# Sheet5.net
KiCad netlist of a schematic drawn in Altium Designer
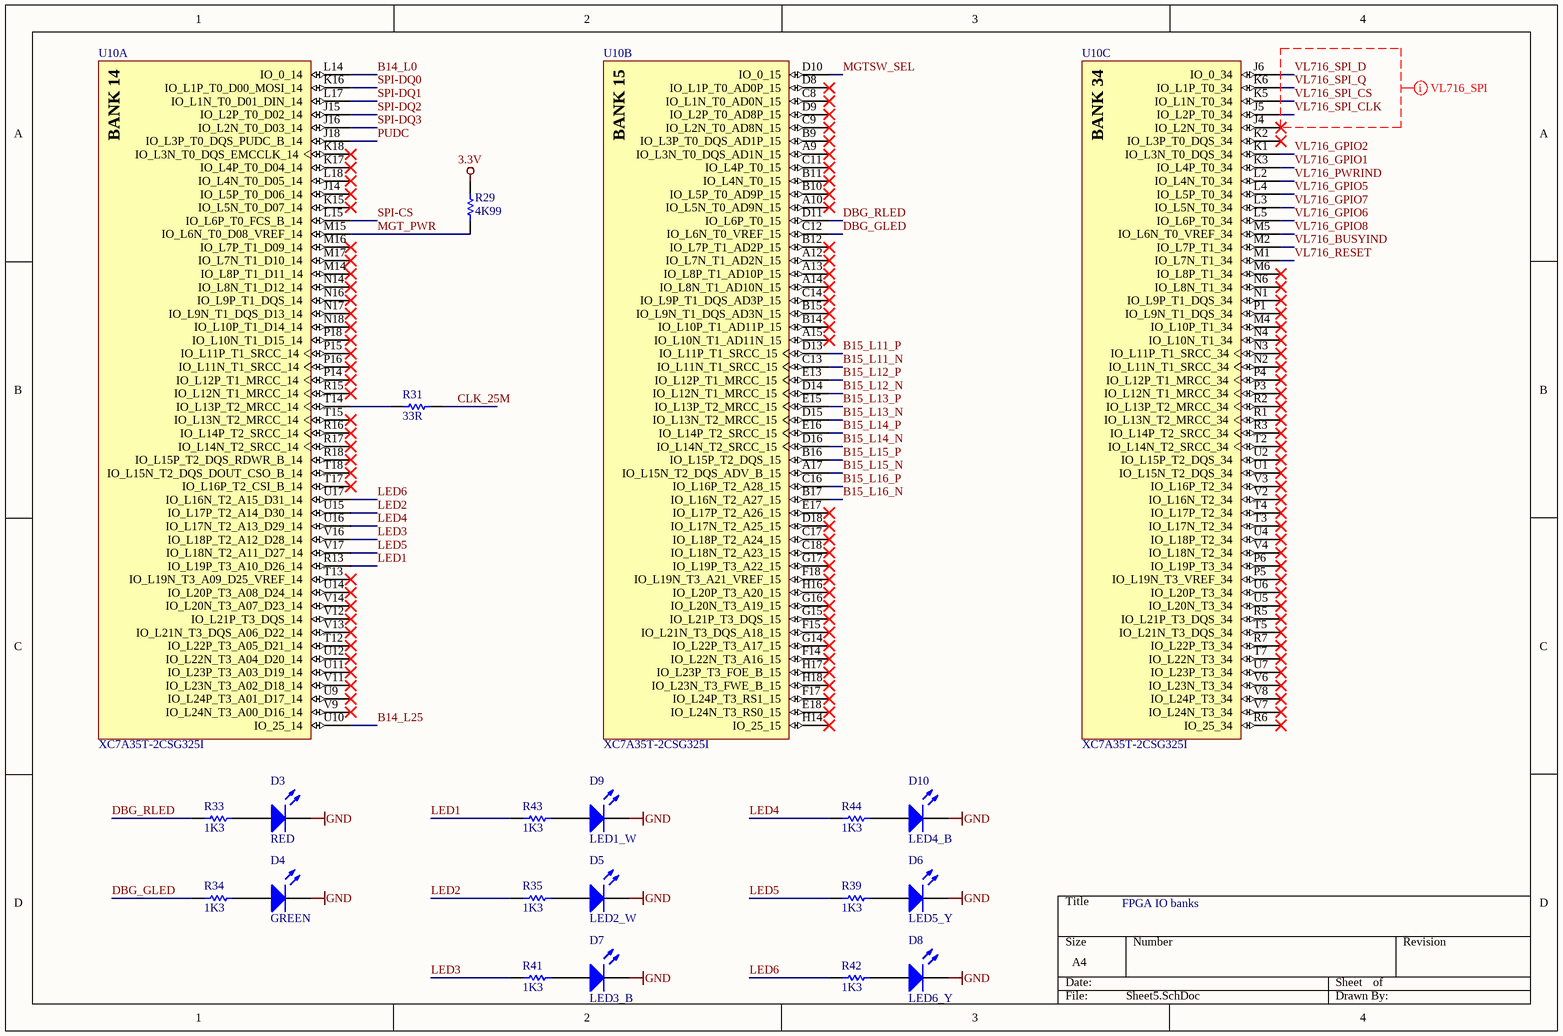
[diagram p0: Sheet5.SchDoc]

(export (version "E")
  (design (tool "Eeschema 10.0.6"))
  (components
    (comp (ref "D3")
      (value "RED")
      (footprint "LEDC2012X10N")
      (description "SMD chip LED")
      (libsource (lib "Integrated_Library") (part "LED0805"))
    )
    (comp (ref "D4")
      (value "GREEN")
      (footprint "LEDC2012X10N")
      (description "SMD chip LED")
      (libsource (lib "Integrated_Library") (part "LED0805"))
    )
    (comp (ref "D5")
      (value "LED2_W")
      (footprint "LEDC2012X10N")
      (description "SMD chip LED")
      (libsource (lib "Integrated_Library") (part "LED0805"))
    )
    (comp (ref "D6")
      (value "LED5_Y")
      (footprint "LEDC2012X10N")
      (description "SMD chip LED")
      (libsource (lib "Integrated_Library") (part "LED0805"))
    )
    (comp (ref "D7")
      (value "LED3_B")
      (footprint "LEDC2012X10N")
      (description "SMD chip LED")
      (libsource (lib "Integrated_Library") (part "LED0805"))
    )
    (comp (ref "D8")
      (value "LED6_Y")
      (footprint "LEDC2012X10N")
      (description "SMD chip LED")
      (libsource (lib "Integrated_Library") (part "LED0805"))
    )
    (comp (ref "D9")
      (value "LED1_W")
      (footprint "LEDC2012X10N")
      (description "SMD chip LED")
      (libsource (lib "Integrated_Library") (part "LED0805"))
    )
    (comp (ref "D10")
      (value "LED4_B")
      (footprint "LEDC2012X10N")
      (description "SMD chip LED")
      (libsource (lib "Integrated_Library") (part "LED0805"))
    )
    (comp (ref "R29")
      (value "4K99")
      (footprint "RESC1005X05N")
      (description "Ceramic Chip Resistor")
      (libsource (lib "Integrated_Library") (part "R0402"))
    )
    (comp (ref "R31")
      (value "33R")
      (footprint "RESC1005X05N")
      (description "Ceramic Chip Resistor")
      (libsource (lib "Integrated_Library") (part "R0402"))
    )
    (comp (ref "R33")
      (value "1K3")
      (footprint "RESC1005X05N")
      (description "Ceramic Chip Resistor")
      (libsource (lib "Integrated_Library") (part "R0402"))
    )
    (comp (ref "R34")
      (value "1K3")
      (footprint "RESC1005X05N")
      (description "Ceramic Chip Resistor")
      (libsource (lib "Integrated_Library") (part "R0402"))
    )
    (comp (ref "R35")
      (value "1K3")
      (footprint "RESC1005X05N")
      (description "Ceramic Chip Resistor")
      (libsource (lib "Integrated_Library") (part "R0402"))
    )
    (comp (ref "R39")
      (value "1K3")
      (footprint "RESC1005X05N")
      (description "Ceramic Chip Resistor")
      (libsource (lib "Integrated_Library") (part "R0402"))
    )
    (comp (ref "R41")
      (value "1K3")
      (footprint "RESC1005X05N")
      (description "Ceramic Chip Resistor")
      (libsource (lib "Integrated_Library") (part "R0402"))
    )
    (comp (ref "R42")
      (value "1K3")
      (footprint "RESC1005X05N")
      (description "Ceramic Chip Resistor")
      (libsource (lib "Integrated_Library") (part "R0402"))
    )
    (comp (ref "R43")
      (value "1K3")
      (footprint "RESC1005X05N")
      (description "Ceramic Chip Resistor")
      (libsource (lib "Integrated_Library") (part "R0402"))
    )
    (comp (ref "R44")
      (value "1K3")
      (footprint "RESC1005X05N")
      (description "Ceramic Chip Resistor")
      (libsource (lib "Integrated_Library") (part "R0402"))
    )
    (comp (ref "U10")
      (value "XC7A35T-2CSG325I")
      (footprint "XC7A35T-2CSG325I")
      (description "Artix-7 FPGA, 150 User I/Os, 4 GTP, 324-Ball BGA, Speed Grade 2, Industrial Grade, Pb-Free")
      (fields (field (name "MANUFACTURER") "Xilinx"))
      (libsource (lib "Integrated_Library") (part "XC7A35T-2CSG325I"))
    )
  )
  (nets
    (net (code "1") (name "/B14_L0") (class "Default")
      (node (ref "U10") (pin "L14") (pinfunction "IO_0_14_L14") (pintype "bidirectional"))
    )
    (net (code "2") (name "/B14_L25") (class "Default")
      (node (ref "U10") (pin "U10") (pinfunction "IO_25_14_U10") (pintype "bidirectional"))
    )
    (net (code "3") (name "/B15_L11_N") (class "Default")
      (node (ref "U10") (pin "C13") (pinfunction "IO_L11N_T1_SRCC_15_C13") (pintype "bidirectional"))
    )
    (net (code "4") (name "/B15_L11_P") (class "Default")
      (node (ref "U10") (pin "D13") (pinfunction "IO_L11P_T1_SRCC_15_D13") (pintype "bidirectional"))
    )
    (net (code "5") (name "/B15_L12_N") (class "Default")
      (node (ref "U10") (pin "D14") (pinfunction "IO_L12N_T1_MRCC_15_D14") (pintype "bidirectional"))
    )
    (net (code "6") (name "/B15_L12_P") (class "Default")
      (node (ref "U10") (pin "E13") (pinfunction "IO_L12P_T1_MRCC_15_E13") (pintype "bidirectional"))
    )
    (net (code "7") (name "/B15_L13_N") (class "Default")
      (node (ref "U10") (pin "D15") (pinfunction "IO_L13N_T2_MRCC_15_D15") (pintype "bidirectional"))
    )
    (net (code "8") (name "/B15_L13_P") (class "Default")
      (node (ref "U10") (pin "E15") (pinfunction "IO_L13P_T2_MRCC_15_E15") (pintype "bidirectional"))
    )
    (net (code "9") (name "/B15_L14_N") (class "Default")
      (node (ref "U10") (pin "D16") (pinfunction "IO_L14N_T2_SRCC_15_D16") (pintype "bidirectional"))
    )
    (net (code "10") (name "/B15_L14_P") (class "Default")
      (node (ref "U10") (pin "E16") (pinfunction "IO_L14P_T2_SRCC_15_E16") (pintype "bidirectional"))
    )
    (net (code "11") (name "/B15_L15_N") (class "Default")
      (node (ref "U10") (pin "A17") (pinfunction "IO_L15N_T2_DQS_ADV_B_15_A17") (pintype "bidirectional"))
    )
    (net (code "12") (name "/B15_L15_P") (class "Default")
      (node (ref "U10") (pin "B16") (pinfunction "IO_L15P_T2_DQS_15_B16") (pintype "bidirectional"))
    )
    (net (code "13") (name "/B15_L16_N") (class "Default")
      (node (ref "U10") (pin "B17") (pinfunction "IO_L16N_T2_A27_15_B17") (pintype "bidirectional"))
    )
    (net (code "14") (name "/B15_L16_P") (class "Default")
      (node (ref "U10") (pin "C16") (pinfunction "IO_L16P_T2_A28_15_C16") (pintype "bidirectional"))
    )
    (net (code "15") (name "/CLK_25M") (class "Default")
      (node (ref "R31") (pin "2") (pinfunction "2_2") (pintype "passive"))
    )
    (net (code "16") (name "/DBG_GLED") (class "Default")
      (node (ref "R34") (pin "2") (pinfunction "2_2") (pintype "passive"))
      (node (ref "U10") (pin "C12") (pinfunction "IO_L6N_T0_VREF_15_C12") (pintype "bidirectional"))
    )
    (net (code "17") (name "/DBG_RLED") (class "Default")
      (node (ref "R33") (pin "2") (pinfunction "2_2") (pintype "passive"))
      (node (ref "U10") (pin "D11") (pinfunction "IO_L6P_T0_15_D11") (pintype "bidirectional"))
    )
    (net (code "18") (name "/LED1") (class "Default")
      (node (ref "R43") (pin "2") (pinfunction "2_2") (pintype "passive"))
      (node (ref "U10") (pin "R13") (pinfunction "IO_L19P_T3_A10_D26_14_R13") (pintype "bidirectional"))
    )
    (net (code "19") (name "/LED2") (class "Default")
      (node (ref "R35") (pin "2") (pinfunction "2_2") (pintype "passive"))
      (node (ref "U10") (pin "U15") (pinfunction "IO_L17P_T2_A14_D30_14_U15") (pintype "bidirectional"))
    )
    (net (code "20") (name "/LED3") (class "Default")
      (node (ref "R41") (pin "2") (pinfunction "2_2") (pintype "passive"))
      (node (ref "U10") (pin "V16") (pinfunction "IO_L18P_T2_A12_D28_14_V16") (pintype "bidirectional"))
    )
    (net (code "21") (name "/LED4") (class "Default")
      (node (ref "R44") (pin "2") (pinfunction "2_2") (pintype "passive"))
      (node (ref "U10") (pin "U16") (pinfunction "IO_L17N_T2_A13_D29_14_U16") (pintype "bidirectional"))
    )
    (net (code "22") (name "/LED5") (class "Default")
      (node (ref "R39") (pin "2") (pinfunction "2_2") (pintype "passive"))
      (node (ref "U10") (pin "V17") (pinfunction "IO_L18N_T2_A11_D27_14_V17") (pintype "bidirectional"))
    )
    (net (code "23") (name "/LED6") (class "Default")
      (node (ref "R42") (pin "2") (pinfunction "2_2") (pintype "passive"))
      (node (ref "U10") (pin "U17") (pinfunction "IO_L16N_T2_A15_D31_14_U17") (pintype "bidirectional"))
    )
    (net (code "24") (name "/MGTSW_SEL") (class "Default")
      (node (ref "U10") (pin "D10") (pinfunction "IO_0_15_D10") (pintype "bidirectional"))
    )
    (net (code "25") (name "/MGT_PWR") (class "Default")
      (node (ref "R29") (pin "2") (pinfunction "2_2") (pintype "passive"))
      (node (ref "U10") (pin "M15") (pinfunction "IO_L6N_T0_D08_VREF_14_M15") (pintype "bidirectional"))
    )
    (net (code "26") (name "/PUDC") (class "Default")
      (node (ref "U10") (pin "J18") (pinfunction "IO_L3P_T0_DQS_PUDC_B_14_J18") (pintype "bidirectional"))
    )
    (net (code "27") (name "/SPI-CS") (class "Default")
      (node (ref "U10") (pin "L15") (pinfunction "IO_L6P_T0_FCS_B_14_L15") (pintype "bidirectional"))
    )
    (net (code "28") (name "/SPI-DQ0") (class "Default")
      (node (ref "U10") (pin "K16") (pinfunction "IO_L1P_T0_D00_MOSI_14_K16") (pintype "bidirectional"))
    )
    (net (code "29") (name "/SPI-DQ1") (class "Default")
      (node (ref "U10") (pin "L17") (pinfunction "IO_L1N_T0_D01_DIN_14_L17") (pintype "bidirectional"))
    )
    (net (code "30") (name "/SPI-DQ2") (class "Default")
      (node (ref "U10") (pin "J15") (pinfunction "IO_L2P_T0_D02_14_J15") (pintype "bidirectional"))
    )
    (net (code "31") (name "/SPI-DQ3") (class "Default")
      (node (ref "U10") (pin "J16") (pinfunction "IO_L2N_T0_D03_14_J16") (pintype "bidirectional"))
    )
    (net (code "32") (name "/VL716_BUSYIND") (class "Default")
      (node (ref "U10") (pin "M2") (pinfunction "IO_L7P_T1_34_M2") (pintype "bidirectional"))
    )
    (net (code "33") (name "/VL716_GPIO1") (class "Default")
      (node (ref "U10") (pin "K3") (pinfunction "IO_L4P_T0_34_K3") (pintype "bidirectional"))
    )
    (net (code "34") (name "/VL716_GPIO2") (class "Default")
      (node (ref "U10") (pin "K1") (pinfunction "IO_L3N_T0_DQS_34_K1") (pintype "bidirectional"))
    )
    (net (code "35") (name "/VL716_GPIO5") (class "Default")
      (node (ref "U10") (pin "L4") (pinfunction "IO_L5P_T0_34_L4") (pintype "bidirectional"))
    )
    (net (code "36") (name "/VL716_GPIO6") (class "Default")
      (node (ref "U10") (pin "L5") (pinfunction "IO_L6P_T0_34_L5") (pintype "bidirectional"))
    )
    (net (code "37") (name "/VL716_GPIO7") (class "Default")
      (node (ref "U10") (pin "L3") (pinfunction "IO_L5N_T0_34_L3") (pintype "bidirectional"))
    )
    (net (code "38") (name "/VL716_GPIO8") (class "Default")
      (node (ref "U10") (pin "M5") (pinfunction "IO_L6N_T0_VREF_34_M5") (pintype "bidirectional"))
    )
    (net (code "39") (name "/VL716_PWRIND") (class "Default")
      (node (ref "U10") (pin "L2") (pinfunction "IO_L4N_T0_34_L2") (pintype "bidirectional"))
    )
    (net (code "40") (name "/VL716_RESET") (class "Default")
      (node (ref "U10") (pin "M1") (pinfunction "IO_L7N_T1_34_M1") (pintype "bidirectional"))
    )
    (net (code "41") (name "/VL716_SPI_CLK") (class "Default")
      (node (ref "U10") (pin "J5") (pinfunction "IO_L2P_T0_34_J5") (pintype "bidirectional"))
    )
    (net (code "42") (name "/VL716_SPI_CS") (class "Default")
      (node (ref "U10") (pin "K5") (pinfunction "IO_L1N_T0_34_K5") (pintype "bidirectional"))
    )
    (net (code "43") (name "/VL716_SPI_D") (class "Default")
      (node (ref "U10") (pin "J6") (pinfunction "IO_0_34_J6") (pintype "bidirectional"))
    )
    (net (code "44") (name "/VL716_SPI_Q") (class "Default")
      (node (ref "U10") (pin "K6") (pinfunction "IO_L1P_T0_34_K6") (pintype "bidirectional"))
    )
    (net (code "45") (name "3.3V") (class "Default")
      (node (ref "R29") (pin "1") (pinfunction "1_1") (pintype "passive"))
    )
    (net (code "46") (name "GND") (class "Default")
      (node (ref "D10") (pin "1") (pinfunction "K_1") (pintype "passive"))
      (node (ref "D3") (pin "1") (pinfunction "K_1") (pintype "passive"))
      (node (ref "D4") (pin "1") (pinfunction "K_1") (pintype "passive"))
      (node (ref "D5") (pin "1") (pinfunction "K_1") (pintype "passive"))
      (node (ref "D6") (pin "1") (pinfunction "K_1") (pintype "passive"))
      (node (ref "D7") (pin "1") (pinfunction "K_1") (pintype "passive"))
      (node (ref "D8") (pin "1") (pinfunction "K_1") (pintype "passive"))
      (node (ref "D9") (pin "1") (pinfunction "K_1") (pintype "passive"))
    )
    (net (code "47") (name "Net-(D3-A)") (class "Default")
      (node (ref "D3") (pin "2") (pinfunction "A_2") (pintype "passive"))
      (node (ref "R33") (pin "1") (pinfunction "1_1") (pintype "passive"))
    )
    (net (code "48") (name "Net-(D4-A)") (class "Default")
      (node (ref "D4") (pin "2") (pinfunction "A_2") (pintype "passive"))
      (node (ref "R34") (pin "1") (pinfunction "1_1") (pintype "passive"))
    )
    (net (code "49") (name "Net-(D5-A)") (class "Default")
      (node (ref "D5") (pin "2") (pinfunction "A_2") (pintype "passive"))
      (node (ref "R35") (pin "1") (pinfunction "1_1") (pintype "passive"))
    )
    (net (code "50") (name "Net-(D6-A)") (class "Default")
      (node (ref "D6") (pin "2") (pinfunction "A_2") (pintype "passive"))
      (node (ref "R39") (pin "1") (pinfunction "1_1") (pintype "passive"))
    )
    (net (code "51") (name "Net-(D7-A)") (class "Default")
      (node (ref "D7") (pin "2") (pinfunction "A_2") (pintype "passive"))
      (node (ref "R41") (pin "1") (pinfunction "1_1") (pintype "passive"))
    )
    (net (code "52") (name "Net-(D8-A)") (class "Default")
      (node (ref "D8") (pin "2") (pinfunction "A_2") (pintype "passive"))
      (node (ref "R42") (pin "1") (pinfunction "1_1") (pintype "passive"))
    )
    (net (code "53") (name "Net-(D9-A)") (class "Default")
      (node (ref "D9") (pin "2") (pinfunction "A_2") (pintype "passive"))
      (node (ref "R43") (pin "1") (pinfunction "1_1") (pintype "passive"))
    )
    (net (code "54") (name "Net-(D10-A)") (class "Default")
      (node (ref "D10") (pin "2") (pinfunction "A_2") (pintype "passive"))
      (node (ref "R44") (pin "1") (pinfunction "1_1") (pintype "passive"))
    )
    (net (code "55") (name "Net-(U10A-IO_L13P_T2_MRCC_14)") (class "Default")
      (node (ref "R31") (pin "1") (pinfunction "1_1") (pintype "passive"))
      (node (ref "U10") (pin "T14") (pinfunction "IO_L13P_T2_MRCC_14_T14") (pintype "bidirectional"))
    )
    (net (code "56") (name "unconnected-(U10A-IO_L3N_T0_DQS_EMCCLK_14-PadK18)") (class "Default")
      (node (ref "U10") (pin "K18") (pinfunction "IO_L3N_T0_DQS_EMCCLK_14_K18") (pintype "bidirectional+no_connect"))
    )
    (net (code "57") (name "unconnected-(U10A-IO_L4N_T0_D05_14-PadL18)") (class "Default")
      (node (ref "U10") (pin "L18") (pinfunction "IO_L4N_T0_D05_14_L18") (pintype "bidirectional+no_connect"))
    )
    (net (code "58") (name "unconnected-(U10A-IO_L4P_T0_D04_14-PadK17)") (class "Default")
      (node (ref "U10") (pin "K17") (pinfunction "IO_L4P_T0_D04_14_K17") (pintype "bidirectional+no_connect"))
    )
    (net (code "59") (name "unconnected-(U10A-IO_L5N_T0_D07_14-PadK15)") (class "Default")
      (node (ref "U10") (pin "K15") (pinfunction "IO_L5N_T0_D07_14_K15") (pintype "bidirectional+no_connect"))
    )
    (net (code "60") (name "unconnected-(U10A-IO_L5P_T0_D06_14-PadJ14)") (class "Default")
      (node (ref "U10") (pin "J14") (pinfunction "IO_L5P_T0_D06_14_J14") (pintype "bidirectional+no_connect"))
    )
    (net (code "61") (name "unconnected-(U10A-IO_L7N_T1_D10_14-PadM17)") (class "Default")
      (node (ref "U10") (pin "M17") (pinfunction "IO_L7N_T1_D10_14_M17") (pintype "bidirectional+no_connect"))
    )
    (net (code "62") (name "unconnected-(U10A-IO_L7P_T1_D09_14-PadM16)") (class "Default")
      (node (ref "U10") (pin "M16") (pinfunction "IO_L7P_T1_D09_14_M16") (pintype "bidirectional+no_connect"))
    )
    (net (code "63") (name "unconnected-(U10A-IO_L8N_T1_D12_14-PadN14)") (class "Default")
      (node (ref "U10") (pin "N14") (pinfunction "IO_L8N_T1_D12_14_N14") (pintype "bidirectional+no_connect"))
    )
    (net (code "64") (name "unconnected-(U10A-IO_L8P_T1_D11_14-PadM14)") (class "Default")
      (node (ref "U10") (pin "M14") (pinfunction "IO_L8P_T1_D11_14_M14") (pintype "bidirectional+no_connect"))
    )
    (net (code "65") (name "unconnected-(U10A-IO_L9N_T1_DQS_D13_14-PadN17)") (class "Default")
      (node (ref "U10") (pin "N17") (pinfunction "IO_L9N_T1_DQS_D13_14_N17") (pintype "bidirectional+no_connect"))
    )
    (net (code "66") (name "unconnected-(U10A-IO_L9P_T1_DQS_14-PadN16)") (class "Default")
      (node (ref "U10") (pin "N16") (pinfunction "IO_L9P_T1_DQS_14_N16") (pintype "bidirectional+no_connect"))
    )
    (net (code "67") (name "unconnected-(U10A-IO_L10N_T1_D15_14-PadP18)") (class "Default")
      (node (ref "U10") (pin "P18") (pinfunction "IO_L10N_T1_D15_14_P18") (pintype "bidirectional+no_connect"))
    )
    (net (code "68") (name "unconnected-(U10A-IO_L10P_T1_D14_14-PadN18)") (class "Default")
      (node (ref "U10") (pin "N18") (pinfunction "IO_L10P_T1_D14_14_N18") (pintype "bidirectional+no_connect"))
    )
    (net (code "69") (name "unconnected-(U10A-IO_L11N_T1_SRCC_14-PadP16)") (class "Default")
      (node (ref "U10") (pin "P16") (pinfunction "IO_L11N_T1_SRCC_14_P16") (pintype "bidirectional+no_connect"))
    )
    (net (code "70") (name "unconnected-(U10A-IO_L11P_T1_SRCC_14-PadP15)") (class "Default")
      (node (ref "U10") (pin "P15") (pinfunction "IO_L11P_T1_SRCC_14_P15") (pintype "bidirectional+no_connect"))
    )
    (net (code "71") (name "unconnected-(U10A-IO_L12N_T1_MRCC_14-PadR15)") (class "Default")
      (node (ref "U10") (pin "R15") (pinfunction "IO_L12N_T1_MRCC_14_R15") (pintype "bidirectional+no_connect"))
    )
    (net (code "72") (name "unconnected-(U10A-IO_L12P_T1_MRCC_14-PadP14)") (class "Default")
      (node (ref "U10") (pin "P14") (pinfunction "IO_L12P_T1_MRCC_14_P14") (pintype "bidirectional+no_connect"))
    )
    (net (code "73") (name "unconnected-(U10A-IO_L13N_T2_MRCC_14-PadT15)") (class "Default")
      (node (ref "U10") (pin "T15") (pinfunction "IO_L13N_T2_MRCC_14_T15") (pintype "bidirectional+no_connect"))
    )
    (net (code "74") (name "unconnected-(U10A-IO_L14N_T2_SRCC_14-PadR17)") (class "Default")
      (node (ref "U10") (pin "R17") (pinfunction "IO_L14N_T2_SRCC_14_R17") (pintype "bidirectional+no_connect"))
    )
    (net (code "75") (name "unconnected-(U10A-IO_L14P_T2_SRCC_14-PadR16)") (class "Default")
      (node (ref "U10") (pin "R16") (pinfunction "IO_L14P_T2_SRCC_14_R16") (pintype "bidirectional+no_connect"))
    )
    (net (code "76") (name "unconnected-(U10A-IO_L15N_T2_DQS_DOUT_CSO_B_14-PadT18)") (class "Default")
      (node (ref "U10") (pin "T18") (pinfunction "IO_L15N_T2_DQS_DOUT_CSO_B_14_T18") (pintype "bidirectional+no_connect"))
    )
    (net (code "77") (name "unconnected-(U10A-IO_L15P_T2_DQS_RDWR_B_14-PadR18)") (class "Default")
      (node (ref "U10") (pin "R18") (pinfunction "IO_L15P_T2_DQS_RDWR_B_14_R18") (pintype "bidirectional+no_connect"))
    )
    (net (code "78") (name "unconnected-(U10A-IO_L16P_T2_CSI_B_14-PadT17)") (class "Default")
      (node (ref "U10") (pin "T17") (pinfunction "IO_L16P_T2_CSI_B_14_T17") (pintype "bidirectional+no_connect"))
    )
    (net (code "79") (name "unconnected-(U10A-IO_L19N_T3_A09_D25_VREF_14-PadT13)") (class "Default")
      (node (ref "U10") (pin "T13") (pinfunction "IO_L19N_T3_A09_D25_VREF_14_T13") (pintype "bidirectional+no_connect"))
    )
    (net (code "80") (name "unconnected-(U10A-IO_L20N_T3_A07_D23_14-PadV14)") (class "Default")
      (node (ref "U10") (pin "V14") (pinfunction "IO_L20N_T3_A07_D23_14_V14") (pintype "bidirectional+no_connect"))
    )
    (net (code "81") (name "unconnected-(U10A-IO_L20P_T3_A08_D24_14-PadU14)") (class "Default")
      (node (ref "U10") (pin "U14") (pinfunction "IO_L20P_T3_A08_D24_14_U14") (pintype "bidirectional+no_connect"))
    )
    (net (code "82") (name "unconnected-(U10A-IO_L21N_T3_DQS_A06_D22_14-PadV13)") (class "Default")
      (node (ref "U10") (pin "V13") (pinfunction "IO_L21N_T3_DQS_A06_D22_14_V13") (pintype "bidirectional+no_connect"))
    )
    (net (code "83") (name "unconnected-(U10A-IO_L21P_T3_DQS_14-PadV12)") (class "Default")
      (node (ref "U10") (pin "V12") (pinfunction "IO_L21P_T3_DQS_14_V12") (pintype "bidirectional+no_connect"))
    )
    (net (code "84") (name "unconnected-(U10A-IO_L22N_T3_A04_D20_14-PadU12)") (class "Default")
      (node (ref "U10") (pin "U12") (pinfunction "IO_L22N_T3_A04_D20_14_U12") (pintype "bidirectional+no_connect"))
    )
    (net (code "85") (name "unconnected-(U10A-IO_L22P_T3_A05_D21_14-PadT12)") (class "Default")
      (node (ref "U10") (pin "T12") (pinfunction "IO_L22P_T3_A05_D21_14_T12") (pintype "bidirectional+no_connect"))
    )
    (net (code "86") (name "unconnected-(U10A-IO_L23N_T3_A02_D18_14-PadV11)") (class "Default")
      (node (ref "U10") (pin "V11") (pinfunction "IO_L23N_T3_A02_D18_14_V11") (pintype "bidirectional+no_connect"))
    )
    (net (code "87") (name "unconnected-(U10A-IO_L23P_T3_A03_D19_14-PadU11)") (class "Default")
      (node (ref "U10") (pin "U11") (pinfunction "IO_L23P_T3_A03_D19_14_U11") (pintype "bidirectional+no_connect"))
    )
    (net (code "88") (name "unconnected-(U10A-IO_L24N_T3_A00_D16_14-PadV9)") (class "Default")
      (node (ref "U10") (pin "V9") (pinfunction "IO_L24N_T3_A00_D16_14_V9") (pintype "bidirectional+no_connect"))
    )
    (net (code "89") (name "unconnected-(U10A-IO_L24P_T3_A01_D17_14-PadU9)") (class "Default")
      (node (ref "U10") (pin "U9") (pinfunction "IO_L24P_T3_A01_D17_14_U9") (pintype "bidirectional+no_connect"))
    )
    (net (code "90") (name "unconnected-(U10B-IO_25_15-PadH14)") (class "Default")
      (node (ref "U10") (pin "H14") (pinfunction "IO_25_15_H14") (pintype "bidirectional+no_connect"))
    )
    (net (code "91") (name "unconnected-(U10B-IO_L1N_T0_AD0N_15-PadC8)") (class "Default")
      (node (ref "U10") (pin "C8") (pinfunction "IO_L1N_T0_AD0N_15_C8") (pintype "bidirectional+no_connect"))
    )
    (net (code "92") (name "unconnected-(U10B-IO_L1P_T0_AD0P_15-PadD8)") (class "Default")
      (node (ref "U10") (pin "D8") (pinfunction "IO_L1P_T0_AD0P_15_D8") (pintype "bidirectional+no_connect"))
    )
    (net (code "93") (name "unconnected-(U10B-IO_L2N_T0_AD8N_15-PadC9)") (class "Default")
      (node (ref "U10") (pin "C9") (pinfunction "IO_L2N_T0_AD8N_15_C9") (pintype "bidirectional+no_connect"))
    )
    (net (code "94") (name "unconnected-(U10B-IO_L2P_T0_AD8P_15-PadD9)") (class "Default")
      (node (ref "U10") (pin "D9") (pinfunction "IO_L2P_T0_AD8P_15_D9") (pintype "bidirectional+no_connect"))
    )
    (net (code "95") (name "unconnected-(U10B-IO_L3N_T0_DQS_AD1N_15-PadA9)") (class "Default")
      (node (ref "U10") (pin "A9") (pinfunction "IO_L3N_T0_DQS_AD1N_15_A9") (pintype "bidirectional+no_connect"))
    )
    (net (code "96") (name "unconnected-(U10B-IO_L3P_T0_DQS_AD1P_15-PadB9)") (class "Default")
      (node (ref "U10") (pin "B9") (pinfunction "IO_L3P_T0_DQS_AD1P_15_B9") (pintype "bidirectional+no_connect"))
    )
    (net (code "97") (name "unconnected-(U10B-IO_L4N_T0_15-PadB11)") (class "Default")
      (node (ref "U10") (pin "B11") (pinfunction "IO_L4N_T0_15_B11") (pintype "bidirectional+no_connect"))
    )
    (net (code "98") (name "unconnected-(U10B-IO_L4P_T0_15-PadC11)") (class "Default")
      (node (ref "U10") (pin "C11") (pinfunction "IO_L4P_T0_15_C11") (pintype "bidirectional+no_connect"))
    )
    (net (code "99") (name "unconnected-(U10B-IO_L5N_T0_AD9N_15-PadA10)") (class "Default")
      (node (ref "U10") (pin "A10") (pinfunction "IO_L5N_T0_AD9N_15_A10") (pintype "bidirectional+no_connect"))
    )
    (net (code "100") (name "unconnected-(U10B-IO_L5P_T0_AD9P_15-PadB10)") (class "Default")
      (node (ref "U10") (pin "B10") (pinfunction "IO_L5P_T0_AD9P_15_B10") (pintype "bidirectional+no_connect"))
    )
    (net (code "101") (name "unconnected-(U10B-IO_L7N_T1_AD2N_15-PadA12)") (class "Default")
      (node (ref "U10") (pin "A12") (pinfunction "IO_L7N_T1_AD2N_15_A12") (pintype "bidirectional+no_connect"))
    )
    (net (code "102") (name "unconnected-(U10B-IO_L7P_T1_AD2P_15-PadB12)") (class "Default")
      (node (ref "U10") (pin "B12") (pinfunction "IO_L7P_T1_AD2P_15_B12") (pintype "bidirectional+no_connect"))
    )
    (net (code "103") (name "unconnected-(U10B-IO_L8N_T1_AD10N_15-PadA14)") (class "Default")
      (node (ref "U10") (pin "A14") (pinfunction "IO_L8N_T1_AD10N_15_A14") (pintype "bidirectional+no_connect"))
    )
    (net (code "104") (name "unconnected-(U10B-IO_L8P_T1_AD10P_15-PadA13)") (class "Default")
      (node (ref "U10") (pin "A13") (pinfunction "IO_L8P_T1_AD10P_15_A13") (pintype "bidirectional+no_connect"))
    )
    (net (code "105") (name "unconnected-(U10B-IO_L9N_T1_DQS_AD3N_15-PadB15)") (class "Default")
      (node (ref "U10") (pin "B15") (pinfunction "IO_L9N_T1_DQS_AD3N_15_B15") (pintype "bidirectional+no_connect"))
    )
    (net (code "106") (name "unconnected-(U10B-IO_L9P_T1_DQS_AD3P_15-PadC14)") (class "Default")
      (node (ref "U10") (pin "C14") (pinfunction "IO_L9P_T1_DQS_AD3P_15_C14") (pintype "bidirectional+no_connect"))
    )
    (net (code "107") (name "unconnected-(U10B-IO_L10N_T1_AD11N_15-PadA15)") (class "Default")
      (node (ref "U10") (pin "A15") (pinfunction "IO_L10N_T1_AD11N_15_A15") (pintype "bidirectional+no_connect"))
    )
    (net (code "108") (name "unconnected-(U10B-IO_L10P_T1_AD11P_15-PadB14)") (class "Default")
      (node (ref "U10") (pin "B14") (pinfunction "IO_L10P_T1_AD11P_15_B14") (pintype "bidirectional+no_connect"))
    )
    (net (code "109") (name "unconnected-(U10B-IO_L17N_T2_A25_15-PadD18)") (class "Default")
      (node (ref "U10") (pin "D18") (pinfunction "IO_L17N_T2_A25_15_D18") (pintype "bidirectional+no_connect"))
    )
    (net (code "110") (name "unconnected-(U10B-IO_L17P_T2_A26_15-PadE17)") (class "Default")
      (node (ref "U10") (pin "E17") (pinfunction "IO_L17P_T2_A26_15_E17") (pintype "bidirectional+no_connect"))
    )
    (net (code "111") (name "unconnected-(U10B-IO_L18N_T2_A23_15-PadC18)") (class "Default")
      (node (ref "U10") (pin "C18") (pinfunction "IO_L18N_T2_A23_15_C18") (pintype "bidirectional+no_connect"))
    )
    (net (code "112") (name "unconnected-(U10B-IO_L18P_T2_A24_15-PadC17)") (class "Default")
      (node (ref "U10") (pin "C17") (pinfunction "IO_L18P_T2_A24_15_C17") (pintype "bidirectional+no_connect"))
    )
    (net (code "113") (name "unconnected-(U10B-IO_L19N_T3_A21_VREF_15-PadF18)") (class "Default")
      (node (ref "U10") (pin "F18") (pinfunction "IO_L19N_T3_A21_VREF_15_F18") (pintype "bidirectional+no_connect"))
    )
    (net (code "114") (name "unconnected-(U10B-IO_L19P_T3_A22_15-PadG17)") (class "Default")
      (node (ref "U10") (pin "G17") (pinfunction "IO_L19P_T3_A22_15_G17") (pintype "bidirectional+no_connect"))
    )
    (net (code "115") (name "unconnected-(U10B-IO_L20N_T3_A19_15-PadG16)") (class "Default")
      (node (ref "U10") (pin "G16") (pinfunction "IO_L20N_T3_A19_15_G16") (pintype "bidirectional+no_connect"))
    )
    (net (code "116") (name "unconnected-(U10B-IO_L20P_T3_A20_15-PadH16)") (class "Default")
      (node (ref "U10") (pin "H16") (pinfunction "IO_L20P_T3_A20_15_H16") (pintype "bidirectional+no_connect"))
    )
    (net (code "117") (name "unconnected-(U10B-IO_L21N_T3_DQS_A18_15-PadF15)") (class "Default")
      (node (ref "U10") (pin "F15") (pinfunction "IO_L21N_T3_DQS_A18_15_F15") (pintype "bidirectional+no_connect"))
    )
    (net (code "118") (name "unconnected-(U10B-IO_L21P_T3_DQS_15-PadG15)") (class "Default")
      (node (ref "U10") (pin "G15") (pinfunction "IO_L21P_T3_DQS_15_G15") (pintype "bidirectional+no_connect"))
    )
    (net (code "119") (name "unconnected-(U10B-IO_L22N_T3_A16_15-PadF14)") (class "Default")
      (node (ref "U10") (pin "F14") (pinfunction "IO_L22N_T3_A16_15_F14") (pintype "bidirectional+no_connect"))
    )
    (net (code "120") (name "unconnected-(U10B-IO_L22P_T3_A17_15-PadG14)") (class "Default")
      (node (ref "U10") (pin "G14") (pinfunction "IO_L22P_T3_A17_15_G14") (pintype "bidirectional+no_connect"))
    )
    (net (code "121") (name "unconnected-(U10B-IO_L23N_T3_FWE_B_15-PadH18)") (class "Default")
      (node (ref "U10") (pin "H18") (pinfunction "IO_L23N_T3_FWE_B_15_H18") (pintype "bidirectional+no_connect"))
    )
    (net (code "122") (name "unconnected-(U10B-IO_L23P_T3_FOE_B_15-PadH17)") (class "Default")
      (node (ref "U10") (pin "H17") (pinfunction "IO_L23P_T3_FOE_B_15_H17") (pintype "bidirectional+no_connect"))
    )
    (net (code "123") (name "unconnected-(U10B-IO_L24N_T3_RS0_15-PadE18)") (class "Default")
      (node (ref "U10") (pin "E18") (pinfunction "IO_L24N_T3_RS0_15_E18") (pintype "bidirectional+no_connect"))
    )
    (net (code "124") (name "unconnected-(U10B-IO_L24P_T3_RS1_15-PadF17)") (class "Default")
      (node (ref "U10") (pin "F17") (pinfunction "IO_L24P_T3_RS1_15_F17") (pintype "bidirectional+no_connect"))
    )
    (net (code "125") (name "unconnected-(U10C-IO_25_34-PadR6)") (class "Default")
      (node (ref "U10") (pin "R6") (pinfunction "IO_25_34_R6") (pintype "bidirectional+no_connect"))
    )
    (net (code "126") (name "unconnected-(U10C-IO_L2N_T0_34-PadJ4)") (class "Default")
      (node (ref "U10") (pin "J4") (pinfunction "IO_L2N_T0_34_J4") (pintype "bidirectional+no_connect"))
    )
    (net (code "127") (name "unconnected-(U10C-IO_L3P_T0_DQS_34-PadK2)") (class "Default")
      (node (ref "U10") (pin "K2") (pinfunction "IO_L3P_T0_DQS_34_K2") (pintype "bidirectional+no_connect"))
    )
    (net (code "128") (name "unconnected-(U10C-IO_L8N_T1_34-PadN6)") (class "Default")
      (node (ref "U10") (pin "N6") (pinfunction "IO_L8N_T1_34_N6") (pintype "bidirectional+no_connect"))
    )
    (net (code "129") (name "unconnected-(U10C-IO_L8P_T1_34-PadM6)") (class "Default")
      (node (ref "U10") (pin "M6") (pinfunction "IO_L8P_T1_34_M6") (pintype "bidirectional+no_connect"))
    )
    (net (code "130") (name "unconnected-(U10C-IO_L9N_T1_DQS_34-PadP1)") (class "Default")
      (node (ref "U10") (pin "P1") (pinfunction "IO_L9N_T1_DQS_34_P1") (pintype "bidirectional+no_connect"))
    )
    (net (code "131") (name "unconnected-(U10C-IO_L9P_T1_DQS_34-PadN1)") (class "Default")
      (node (ref "U10") (pin "N1") (pinfunction "IO_L9P_T1_DQS_34_N1") (pintype "bidirectional+no_connect"))
    )
    (net (code "132") (name "unconnected-(U10C-IO_L10N_T1_34-PadN4)") (class "Default")
      (node (ref "U10") (pin "N4") (pinfunction "IO_L10N_T1_34_N4") (pintype "bidirectional+no_connect"))
    )
    (net (code "133") (name "unconnected-(U10C-IO_L10P_T1_34-PadM4)") (class "Default")
      (node (ref "U10") (pin "M4") (pinfunction "IO_L10P_T1_34_M4") (pintype "bidirectional+no_connect"))
    )
    (net (code "134") (name "unconnected-(U10C-IO_L11N_T1_SRCC_34-PadN2)") (class "Default")
      (node (ref "U10") (pin "N2") (pinfunction "IO_L11N_T1_SRCC_34_N2") (pintype "bidirectional+no_connect"))
    )
    (net (code "135") (name "unconnected-(U10C-IO_L11P_T1_SRCC_34-PadN3)") (class "Default")
      (node (ref "U10") (pin "N3") (pinfunction "IO_L11P_T1_SRCC_34_N3") (pintype "bidirectional+no_connect"))
    )
    (net (code "136") (name "unconnected-(U10C-IO_L12N_T1_MRCC_34-PadP3)") (class "Default")
      (node (ref "U10") (pin "P3") (pinfunction "IO_L12N_T1_MRCC_34_P3") (pintype "bidirectional+no_connect"))
    )
    (net (code "137") (name "unconnected-(U10C-IO_L12P_T1_MRCC_34-PadP4)") (class "Default")
      (node (ref "U10") (pin "P4") (pinfunction "IO_L12P_T1_MRCC_34_P4") (pintype "bidirectional+no_connect"))
    )
    (net (code "138") (name "unconnected-(U10C-IO_L13N_T2_MRCC_34-PadR1)") (class "Default")
      (node (ref "U10") (pin "R1") (pinfunction "IO_L13N_T2_MRCC_34_R1") (pintype "bidirectional+no_connect"))
    )
    (net (code "139") (name "unconnected-(U10C-IO_L13P_T2_MRCC_34-PadR2)") (class "Default")
      (node (ref "U10") (pin "R2") (pinfunction "IO_L13P_T2_MRCC_34_R2") (pintype "bidirectional+no_connect"))
    )
    (net (code "140") (name "unconnected-(U10C-IO_L14N_T2_SRCC_34-PadT2)") (class "Default")
      (node (ref "U10") (pin "T2") (pinfunction "IO_L14N_T2_SRCC_34_T2") (pintype "bidirectional+no_connect"))
    )
    (net (code "141") (name "unconnected-(U10C-IO_L14P_T2_SRCC_34-PadR3)") (class "Default")
      (node (ref "U10") (pin "R3") (pinfunction "IO_L14P_T2_SRCC_34_R3") (pintype "bidirectional+no_connect"))
    )
    (net (code "142") (name "unconnected-(U10C-IO_L15N_T2_DQS_34-PadU1)") (class "Default")
      (node (ref "U10") (pin "U1") (pinfunction "IO_L15N_T2_DQS_34_U1") (pintype "bidirectional+no_connect"))
    )
    (net (code "143") (name "unconnected-(U10C-IO_L15P_T2_DQS_34-PadU2)") (class "Default")
      (node (ref "U10") (pin "U2") (pinfunction "IO_L15P_T2_DQS_34_U2") (pintype "bidirectional+no_connect"))
    )
    (net (code "144") (name "unconnected-(U10C-IO_L16N_T2_34-PadV2)") (class "Default")
      (node (ref "U10") (pin "V2") (pinfunction "IO_L16N_T2_34_V2") (pintype "bidirectional+no_connect"))
    )
    (net (code "145") (name "unconnected-(U10C-IO_L16P_T2_34-PadV3)") (class "Default")
      (node (ref "U10") (pin "V3") (pinfunction "IO_L16P_T2_34_V3") (pintype "bidirectional+no_connect"))
    )
    (net (code "146") (name "unconnected-(U10C-IO_L17N_T2_34-PadT3)") (class "Default")
      (node (ref "U10") (pin "T3") (pinfunction "IO_L17N_T2_34_T3") (pintype "bidirectional+no_connect"))
    )
    (net (code "147") (name "unconnected-(U10C-IO_L17P_T2_34-PadT4)") (class "Default")
      (node (ref "U10") (pin "T4") (pinfunction "IO_L17P_T2_34_T4") (pintype "bidirectional+no_connect"))
    )
    (net (code "148") (name "unconnected-(U10C-IO_L18N_T2_34-PadV4)") (class "Default")
      (node (ref "U10") (pin "V4") (pinfunction "IO_L18N_T2_34_V4") (pintype "bidirectional+no_connect"))
    )
    (net (code "149") (name "unconnected-(U10C-IO_L18P_T2_34-PadU4)") (class "Default")
      (node (ref "U10") (pin "U4") (pinfunction "IO_L18P_T2_34_U4") (pintype "bidirectional+no_connect"))
    )
    (net (code "150") (name "unconnected-(U10C-IO_L19N_T3_VREF_34-PadP5)") (class "Default")
      (node (ref "U10") (pin "P5") (pinfunction "IO_L19N_T3_VREF_34_P5") (pintype "bidirectional+no_connect"))
    )
    (net (code "151") (name "unconnected-(U10C-IO_L19P_T3_34-PadP6)") (class "Default")
      (node (ref "U10") (pin "P6") (pinfunction "IO_L19P_T3_34_P6") (pintype "bidirectional+no_connect"))
    )
    (net (code "152") (name "unconnected-(U10C-IO_L20N_T3_34-PadU5)") (class "Default")
      (node (ref "U10") (pin "U5") (pinfunction "IO_L20N_T3_34_U5") (pintype "bidirectional+no_connect"))
    )
    (net (code "153") (name "unconnected-(U10C-IO_L20P_T3_34-PadU6)") (class "Default")
      (node (ref "U10") (pin "U6") (pinfunction "IO_L20P_T3_34_U6") (pintype "bidirectional+no_connect"))
    )
    (net (code "154") (name "unconnected-(U10C-IO_L21N_T3_DQS_34-PadT5)") (class "Default")
      (node (ref "U10") (pin "T5") (pinfunction "IO_L21N_T3_DQS_34_T5") (pintype "bidirectional+no_connect"))
    )
    (net (code "155") (name "unconnected-(U10C-IO_L21P_T3_DQS_34-PadR5)") (class "Default")
      (node (ref "U10") (pin "R5") (pinfunction "IO_L21P_T3_DQS_34_R5") (pintype "bidirectional+no_connect"))
    )
    (net (code "156") (name "unconnected-(U10C-IO_L22N_T3_34-PadT7)") (class "Default")
      (node (ref "U10") (pin "T7") (pinfunction "IO_L22N_T3_34_T7") (pintype "bidirectional+no_connect"))
    )
    (net (code "157") (name "unconnected-(U10C-IO_L22P_T3_34-PadR7)") (class "Default")
      (node (ref "U10") (pin "R7") (pinfunction "IO_L22P_T3_34_R7") (pintype "bidirectional+no_connect"))
    )
    (net (code "158") (name "unconnected-(U10C-IO_L23N_T3_34-PadV6)") (class "Default")
      (node (ref "U10") (pin "V6") (pinfunction "IO_L23N_T3_34_V6") (pintype "bidirectional+no_connect"))
    )
    (net (code "159") (name "unconnected-(U10C-IO_L23P_T3_34-PadU7)") (class "Default")
      (node (ref "U10") (pin "U7") (pinfunction "IO_L23P_T3_34_U7") (pintype "bidirectional+no_connect"))
    )
    (net (code "160") (name "unconnected-(U10C-IO_L24N_T3_34-PadV7)") (class "Default")
      (node (ref "U10") (pin "V7") (pinfunction "IO_L24N_T3_34_V7") (pintype "bidirectional+no_connect"))
    )
    (net (code "161") (name "unconnected-(U10C-IO_L24P_T3_34-PadV8)") (class "Default")
      (node (ref "U10") (pin "V8") (pinfunction "IO_L24P_T3_34_V8") (pintype "bidirectional+no_connect"))
    )
  )
)
